# MGTAVTT.net
KiCad netlist of a schematic drawn in Altium Designer
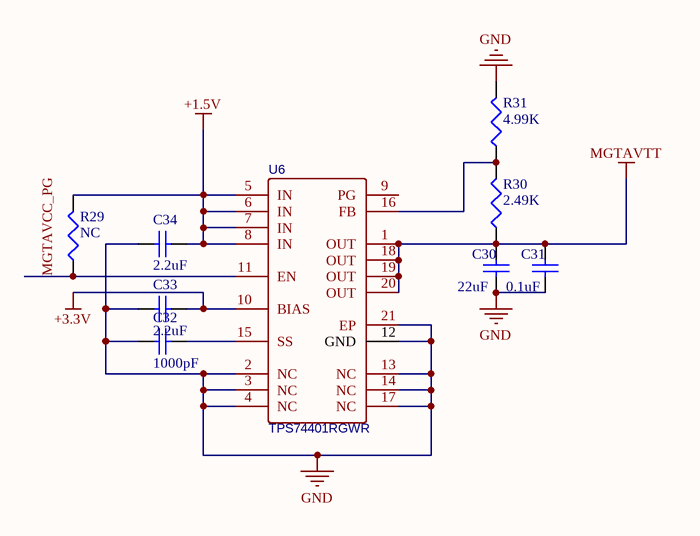
[diagram p0: MGTAVTT.SchDoc]

(export (version "E")
  (design (tool "Eeschema 10.0.6"))
  (components
    (comp (ref "C30")
      (value "22uF")
      (footprint "C1210")
      (description "Capacitor (Semiconductor SIM Model)")
      (fields (field (name "Comment") "Cap Semi") (field (name "PUBLISHER") "Altium Limited"))
      (libsource (lib "Miscellaneous Devices") (part "Cap Semi"))
    )
    (comp (ref "C31")
      (value "0.1uF")
      (footprint "C1210")
      (description "Capacitor (Semiconductor SIM Model)")
      (fields (field (name "Comment") "Cap Semi") (field (name "PUBLISHER") "Altium Limited"))
      (libsource (lib "Miscellaneous Devices") (part "Cap Semi"))
    )
    (comp (ref "C32")
      (value "1000pF")
      (footprint "C1210")
      (description "Capacitor (Semiconductor SIM Model)")
      (fields (field (name "Comment") "Cap Semi") (field (name "PUBLISHER") "Altium Limited"))
      (libsource (lib "Miscellaneous Devices") (part "Cap Semi"))
    )
    (comp (ref "C33")
      (value "2.2uF")
      (footprint "C1210")
      (description "Capacitor (Semiconductor SIM Model)")
      (fields (field (name "Comment") "Cap Semi") (field (name "PUBLISHER") "Altium Limited"))
      (libsource (lib "Miscellaneous Devices") (part "Cap Semi"))
    )
    (comp (ref "C34")
      (value "2.2uF")
      (footprint "C1210")
      (description "Capacitor (Semiconductor SIM Model)")
      (fields (field (name "Comment") "Cap Semi") (field (name "PUBLISHER") "Altium Limited"))
      (libsource (lib "Miscellaneous Devices") (part "Cap Semi"))
    )
    (comp (ref "R29")
      (value "NC")
      (footprint "J1-0603")
      (description "Resistor")
      (fields (field (name "Comment") "Res3") (field (name "PUBLISHER") "Altium Limited"))
      (libsource (lib "Miscellaneous Devices") (part "Res3"))
    )
    (comp (ref "R30")
      (value "2.49K")
      (footprint "J1-0603")
      (description "Resistor")
      (fields (field (name "Comment") "Res3") (field (name "PUBLISHER") "Altium Limited"))
      (libsource (lib "Miscellaneous Devices") (part "Res3"))
    )
    (comp (ref "R31")
      (value "4.99K")
      (footprint "J1-0603")
      (description "Resistor")
      (fields (field (name "Comment") "Res3") (field (name "PUBLISHER") "Altium Limited"))
      (libsource (lib "Miscellaneous Devices") (part "Res3"))
    )
    (comp (ref "U6")
      (value "TPS74401RGWR")
      (footprint "VQFN-20_L5.0-W5.0-P0.65-TL-EP")
      (fields (field (name "BOM_SUPPLIER PART") "C138728") (field (name "CONTRIBUTOR") "LCSC"))
      (libsource (lib "power_chip") (part "TPS74401RGWR"))
    )
  )
  (nets
    (net (code "1") (name "+1.5V") (class "Default")
      (node (ref "C34") (pin "1") (pinfunction "1_1") (pintype "passive"))
      (node (ref "R29") (pin "2") (pinfunction "2_2") (pintype "passive"))
      (node (ref "U6") (pin "5") (pinfunction "IN_5") (pintype "passive"))
      (node (ref "U6") (pin "6") (pinfunction "IN_6") (pintype "passive"))
      (node (ref "U6") (pin "7") (pinfunction "IN_7") (pintype "passive"))
      (node (ref "U6") (pin "8") (pinfunction "IN_8") (pintype "passive"))
    )
    (net (code "2") (name "+3.3V") (class "Default")
      (node (ref "C33") (pin "1") (pinfunction "1_1") (pintype "passive"))
      (node (ref "U6") (pin "10") (pinfunction "BIAS_10") (pintype "passive"))
    )
    (net (code "3") (name "/MGTAVCC_PG") (class "Default")
      (node (ref "R29") (pin "1") (pinfunction "1_1") (pintype "passive"))
      (node (ref "U6") (pin "11") (pinfunction "EN_11") (pintype "passive"))
    )
    (net (code "4") (name "GND") (class "Default")
      (node (ref "C30") (pin "1") (pinfunction "1_1") (pintype "passive"))
      (node (ref "C31") (pin "1") (pinfunction "1_1") (pintype "passive"))
      (node (ref "C32") (pin "2") (pinfunction "2_2") (pintype "passive"))
      (node (ref "C33") (pin "2") (pinfunction "2_2") (pintype "passive"))
      (node (ref "C34") (pin "2") (pinfunction "2_2") (pintype "passive"))
      (node (ref "R31") (pin "2") (pinfunction "2_2") (pintype "passive"))
      (node (ref "U6") (pin "12") (pinfunction "GND_12") (pintype "passive"))
      (node (ref "U6") (pin "13") (pinfunction "NC_13") (pintype "passive"))
      (node (ref "U6") (pin "14") (pinfunction "NC_14") (pintype "passive"))
      (node (ref "U6") (pin "17") (pinfunction "NC_17") (pintype "passive"))
      (node (ref "U6") (pin "2") (pinfunction "NC_2") (pintype "passive"))
      (node (ref "U6") (pin "21") (pinfunction "EP_21") (pintype "passive"))
      (node (ref "U6") (pin "3") (pinfunction "NC_3") (pintype "passive"))
      (node (ref "U6") (pin "4") (pinfunction "NC_4") (pintype "passive"))
    )
    (net (code "5") (name "MGTAVTT") (class "Default")
      (node (ref "C30") (pin "2") (pinfunction "2_2") (pintype "passive"))
      (node (ref "C31") (pin "2") (pinfunction "2_2") (pintype "passive"))
      (node (ref "R30") (pin "1") (pinfunction "1_1") (pintype "passive"))
      (node (ref "U6") (pin "1") (pinfunction "OUT_1") (pintype "passive"))
      (node (ref "U6") (pin "18") (pinfunction "OUT_18") (pintype "passive"))
      (node (ref "U6") (pin "19") (pinfunction "OUT_19") (pintype "passive"))
      (node (ref "U6") (pin "20") (pinfunction "OUT_20") (pintype "passive"))
    )
    (net (code "6") (name "Net-(U6-FB)") (class "Default")
      (node (ref "R30") (pin "2") (pinfunction "2_2") (pintype "passive"))
      (node (ref "R31") (pin "1") (pinfunction "1_1") (pintype "passive"))
      (node (ref "U6") (pin "16") (pinfunction "FB_16") (pintype "passive"))
    )
    (net (code "7") (name "Net-(U6-SS)") (class "Default")
      (node (ref "C32") (pin "1") (pinfunction "1_1") (pintype "passive"))
      (node (ref "U6") (pin "15") (pinfunction "SS_15") (pintype "passive"))
    )
    (net (code "8") (name "unconnected-(U6-PG-Pad9)") (class "Default")
      (node (ref "U6") (pin "9") (pinfunction "PG_9") (pintype "passive"))
    )
  )
)
